# LED_battary.net
KiCad netlist of a schematic drawn in EAGLE
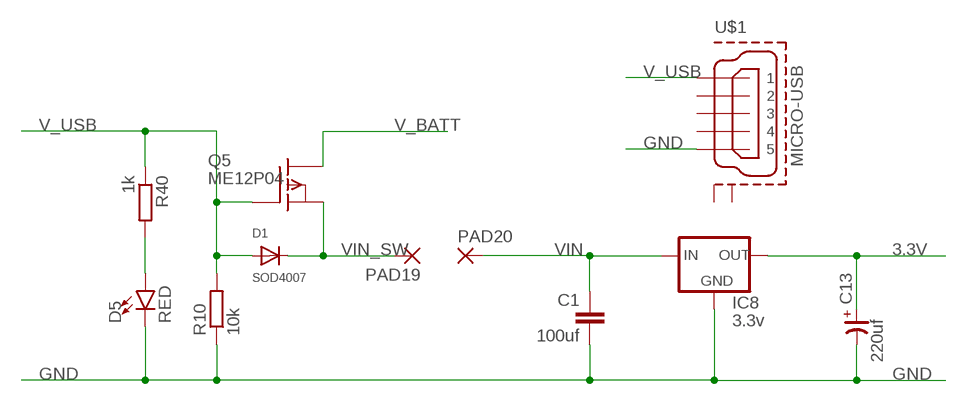
[diagram p0: schematic, sheet 1]
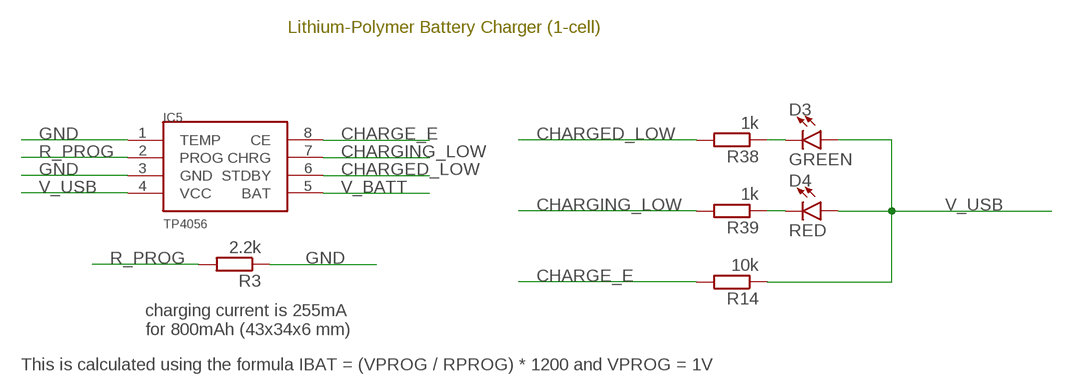
[diagram p1: schematic, sheet 2]
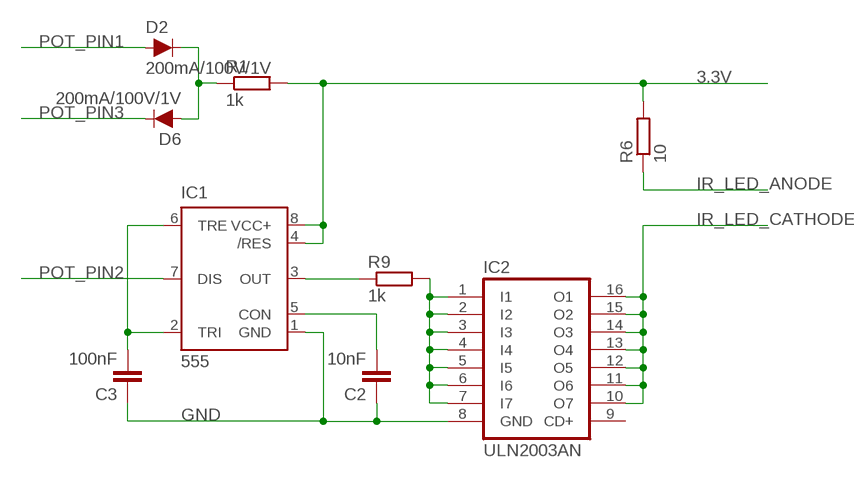
[diagram p2: schematic, sheet 3]
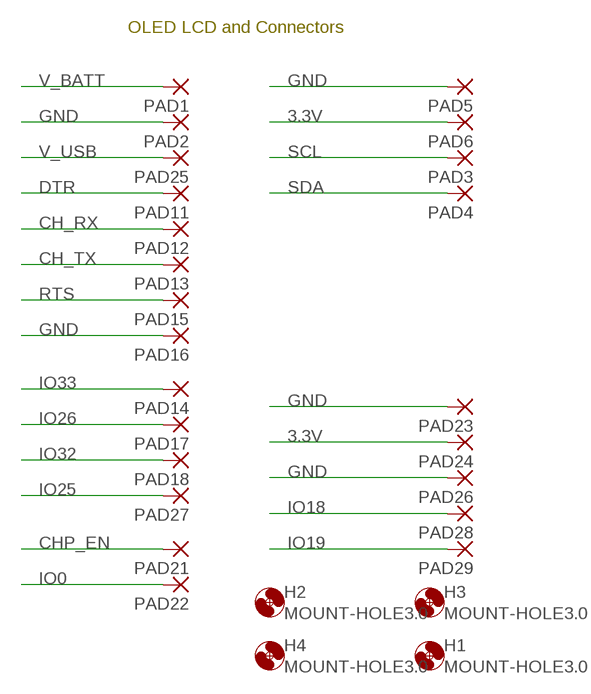
[diagram p3: schematic, sheet 4]

(export (version "E")
  (design (tool "Eeschema 10.0.6"))
  (components
    (comp (ref "D3")
      (value "GREEN")
      (footprint "eagle-import:LED-1206")
      (libsource (lib "eagle-import") (part "LED-GREEN1206"))
    )
    (comp (ref "D4")
      (value "RED")
      (footprint "eagle-import:LED-1206")
      (libsource (lib "eagle-import") (part "LED-GREEN1206"))
    )
    (comp (ref "IC5")
      (value "TP4056")
      (footprint "eagle-import:SOP-8")
      (libsource (lib "eagle-import") (part "TP4056"))
    )
    (comp (ref "R3")
      (value "2.2k")
      (footprint "eagle-import:0207_10")
      (libsource (lib "eagle-import") (part "R-EU_0207/10"))
    )
    (comp (ref "R14")
      (value "10k")
      (footprint "eagle-import:0207_10")
      (libsource (lib "eagle-import") (part "R-EU_0207/10"))
    )
    (comp (ref "R38")
      (value "1k")
      (footprint "eagle-import:0207_10")
      (libsource (lib "eagle-import") (part "R-EU_0207/10"))
    )
    (comp (ref "R39")
      (value "1k")
      (footprint "eagle-import:0207_10")
      (libsource (lib "eagle-import") (part "R-EU_0207/10"))
    )
    (comp (ref "C1")
      (value "100uf")
      (footprint "eagle-import:C1206K")
      (libsource (lib "eagle-import") (part "C-EUC1206K"))
    )
    (comp (ref "C13")
      (value "220uf")
      (footprint "eagle-import:7343_T")
      (libsource (lib "eagle-import") (part "CP-7343"))
    )
    (comp (ref "D1")
      (value "SOD4007")
      (footprint "eagle-import:SOD-123FL")
      (libsource (lib "eagle-import") (part "DIODE_SOD-123FL"))
    )
    (comp (ref "D5")
      (value "RED")
      (footprint "eagle-import:LED-1206")
      (libsource (lib "eagle-import") (part "LED-GREEN1206"))
    )
    (comp (ref "IC8")
      (value "3.3v")
      (footprint "eagle-import:TO252")
      (libsource (lib "eagle-import") (part "LM1117TO252"))
    )
    (comp (ref "PAD19")
      (value "SMD2")
      (footprint "eagle-import:SMD1,27-2,54")
      (libsource (lib "eagle-import") (part "SMD2"))
    )
    (comp (ref "PAD20")
      (value "SMD2")
      (footprint "eagle-import:SMD1,27-2,54")
      (libsource (lib "eagle-import") (part "SMD2"))
    )
    (comp (ref "Q5")
      (value "ME12P04")
      (footprint "eagle-import:TO220")
      (libsource (lib "eagle-import") (part "IRF9530"))
    )
    (comp (ref "R10")
      (value "10k")
      (footprint "eagle-import:0207_10")
      (libsource (lib "eagle-import") (part "R-EU_0207/10"))
    )
    (comp (ref "R40")
      (value "1k")
      (footprint "eagle-import:0207_10")
      (libsource (lib "eagle-import") (part "R-EU_0207/10"))
    )
    (comp (ref "U$1")
      (value "MICRO-USB")
      (footprint "eagle-import:47589-0001")
      (libsource (lib "eagle-import") (part "MICRO-USB-RECEPTACLE47589-0001"))
    )
    (comp (ref "H1")
      (value "MOUNT-HOLE3.0")
      (footprint "eagle-import:3,0")
      (libsource (lib "eagle-import") (part "MOUNT-HOLE3.0"))
    )
    (comp (ref "H2")
      (value "MOUNT-HOLE3.0")
      (footprint "eagle-import:3,0")
      (libsource (lib "eagle-import") (part "MOUNT-HOLE3.0"))
    )
    (comp (ref "H3")
      (value "MOUNT-HOLE3.0")
      (footprint "eagle-import:3,0")
      (libsource (lib "eagle-import") (part "MOUNT-HOLE3.0"))
    )
    (comp (ref "H4")
      (value "MOUNT-HOLE3.0")
      (footprint "eagle-import:3,0")
      (libsource (lib "eagle-import") (part "MOUNT-HOLE3.0"))
    )
    (comp (ref "PAD1")
      (value "WIREPADSMD5-2,5")
      (footprint "eagle-import:5-2,5")
      (libsource (lib "eagle-import") (part "WIREPADSMD5-2,5"))
    )
    (comp (ref "PAD2")
      (value "WIREPADSMD5-2,5")
      (footprint "eagle-import:5-2,5")
      (libsource (lib "eagle-import") (part "WIREPADSMD5-2,5"))
    )
    (comp (ref "PAD3")
      (value "SMD2")
      (footprint "eagle-import:SMD1,27-2,54")
      (libsource (lib "eagle-import") (part "SMD2"))
    )
    (comp (ref "PAD4")
      (value "SMD2")
      (footprint "eagle-import:SMD1,27-2,54")
      (libsource (lib "eagle-import") (part "SMD2"))
    )
    (comp (ref "PAD5")
      (value "SMD2")
      (footprint "eagle-import:SMD1,27-2,54")
      (libsource (lib "eagle-import") (part "SMD2"))
    )
    (comp (ref "PAD6")
      (value "SMD2")
      (footprint "eagle-import:SMD1,27-2,54")
      (libsource (lib "eagle-import") (part "SMD2"))
    )
    (comp (ref "PAD11")
      (value "SMD2")
      (footprint "eagle-import:SMD1,27-2,54")
      (libsource (lib "eagle-import") (part "SMD2"))
    )
    (comp (ref "PAD12")
      (value "SMD2")
      (footprint "eagle-import:SMD1,27-2,54")
      (libsource (lib "eagle-import") (part "SMD2"))
    )
    (comp (ref "PAD13")
      (value "SMD2")
      (footprint "eagle-import:SMD1,27-2,54")
      (libsource (lib "eagle-import") (part "SMD2"))
    )
    (comp (ref "PAD14")
      (value "SMD2")
      (footprint "eagle-import:SMD1,27-2,54")
      (libsource (lib "eagle-import") (part "SMD2"))
    )
    (comp (ref "PAD15")
      (value "SMD2")
      (footprint "eagle-import:SMD1,27-2,54")
      (libsource (lib "eagle-import") (part "SMD2"))
    )
    (comp (ref "PAD16")
      (value "SMD2")
      (footprint "eagle-import:SMD1,27-2,54")
      (libsource (lib "eagle-import") (part "SMD2"))
    )
    (comp (ref "PAD17")
      (value "SMD2")
      (footprint "eagle-import:SMD1,27-2,54")
      (libsource (lib "eagle-import") (part "SMD2"))
    )
    (comp (ref "PAD18")
      (value "SMD2")
      (footprint "eagle-import:SMD1,27-2,54")
      (libsource (lib "eagle-import") (part "SMD2"))
    )
    (comp (ref "PAD21")
      (value "SMD2")
      (footprint "eagle-import:SMD1,27-2,54")
      (libsource (lib "eagle-import") (part "SMD2"))
    )
    (comp (ref "PAD22")
      (value "SMD2")
      (footprint "eagle-import:SMD1,27-2,54")
      (libsource (lib "eagle-import") (part "SMD2"))
    )
    (comp (ref "PAD23")
      (value "SMD2")
      (footprint "eagle-import:SMD1,27-2,54")
      (libsource (lib "eagle-import") (part "SMD2"))
    )
    (comp (ref "PAD24")
      (value "SMD2")
      (footprint "eagle-import:SMD1,27-2,54")
      (libsource (lib "eagle-import") (part "SMD2"))
    )
    (comp (ref "PAD25")
      (value "SMD2")
      (footprint "eagle-import:SMD1,27-2,54")
      (libsource (lib "eagle-import") (part "SMD2"))
    )
    (comp (ref "PAD26")
      (value "SMD2")
      (footprint "eagle-import:SMD1,27-2,54")
      (libsource (lib "eagle-import") (part "SMD2"))
    )
    (comp (ref "PAD27")
      (value "SMD2")
      (footprint "eagle-import:SMD1,27-2,54")
      (libsource (lib "eagle-import") (part "SMD2"))
    )
    (comp (ref "PAD28")
      (value "SMD2")
      (footprint "eagle-import:SMD1,27-2,54")
      (libsource (lib "eagle-import") (part "SMD2"))
    )
    (comp (ref "PAD29")
      (value "SMD2")
      (footprint "eagle-import:SMD1,27-2,54")
      (libsource (lib "eagle-import") (part "SMD2"))
    )
    (comp (ref "C2")
      (value "10nF")
      (footprint "eagle-import:C1206K")
      (libsource (lib "eagle-import") (part "C-EUC1206K"))
    )
    (comp (ref "C3")
      (value "100nF")
      (footprint "eagle-import:C1206K")
      (libsource (lib "eagle-import") (part "C-EUC1206K"))
    )
    (comp (ref "D2")
      (value "200mA/100V/1V")
      (footprint "eagle-import:DIODE-1N4148")
      (libsource (lib "eagle-import") (part "DIODE-1N4148"))
    )
    (comp (ref "D6")
      (value "200mA/100V/1V")
      (footprint "eagle-import:DIODE-1N4148")
      (libsource (lib "eagle-import") (part "DIODE-1N4148"))
    )
    (comp (ref "IC1")
      (value "555")
      (footprint "eagle-import:DIP08")
      (libsource (lib "eagle-import") (part "555P"))
    )
    (comp (ref "IC2")
      (value "ULN2003AN")
      (footprint "eagle-import:DIL16")
      (libsource (lib "eagle-import") (part "ULN2003AN"))
    )
    (comp (ref "R1")
      (value "1k")
      (footprint "eagle-import:0207_10")
      (libsource (lib "eagle-import") (part "R-EU_0207/10"))
    )
    (comp (ref "R6")
      (value "10")
      (footprint "eagle-import:0207_10")
      (libsource (lib "eagle-import") (part "R-EU_0207/10"))
    )
    (comp (ref "R9")
      (value "1k")
      (footprint "eagle-import:0207_10")
      (libsource (lib "eagle-import") (part "R-EU_0207/10"))
    )
  )
  (nets
    (net (code "1") (name "3.3V") (class "Default")
      (node (ref "C13") (pin "+") (pinfunction "+_+") (pintype "passive"))
      (node (ref "IC1") (pin "4") (pinfunction "/RES_4") (pintype "input"))
      (node (ref "IC1") (pin "8") (pinfunction "VCC+_8") (pintype "power_in"))
      (node (ref "IC8") (pin "3") (pinfunction "OUT_3") (pintype "passive"))
      (node (ref "PAD24") (pin "1") (pinfunction "P_1") (pintype "passive"))
      (node (ref "PAD6") (pin "1") (pinfunction "P_1") (pintype "passive"))
      (node (ref "R1") (pin "2") (pinfunction "2_2") (pintype "passive"))
      (node (ref "R6") (pin "2") (pinfunction "2_2") (pintype "passive"))
    )
    (net (code "2") (name "CHARGED_LOW") (class "Default")
      (node (ref "IC5") (pin "6") (pinfunction "STDBY_6") (pintype "bidirectional"))
      (node (ref "R38") (pin "2") (pinfunction "2_2") (pintype "passive"))
    )
    (net (code "3") (name "CHARGE_E") (class "Default")
      (node (ref "IC5") (pin "8") (pinfunction "CE_8") (pintype "bidirectional"))
      (node (ref "R14") (pin "2") (pinfunction "2_2") (pintype "passive"))
    )
    (net (code "4") (name "CHARGING_LOW") (class "Default")
      (node (ref "IC5") (pin "7") (pinfunction "CHRG_7") (pintype "bidirectional"))
      (node (ref "R39") (pin "2") (pinfunction "2_2") (pintype "passive"))
    )
    (net (code "5") (name "CHP_EN") (class "Default")
      (node (ref "PAD21") (pin "1") (pinfunction "P_1") (pintype "passive"))
    )
    (net (code "6") (name "CH_RX") (class "Default")
      (node (ref "PAD12") (pin "1") (pinfunction "P_1") (pintype "passive"))
    )
    (net (code "7") (name "CH_TX") (class "Default")
      (node (ref "PAD13") (pin "1") (pinfunction "P_1") (pintype "passive"))
    )
    (net (code "8") (name "DTR") (class "Default")
      (node (ref "PAD11") (pin "1") (pinfunction "P_1") (pintype "passive"))
    )
    (net (code "9") (name "GND") (class "Default")
      (node (ref "C1") (pin "2") (pinfunction "2_2") (pintype "passive"))
      (node (ref "C13") (pin "-") (pinfunction "-_-") (pintype "passive"))
      (node (ref "C2") (pin "1") (pinfunction "1_1") (pintype "passive"))
      (node (ref "C3") (pin "1") (pinfunction "1_1") (pintype "passive"))
      (node (ref "D5") (pin "C") (pinfunction "C_C") (pintype "passive"))
      (node (ref "IC1") (pin "1") (pinfunction "GND_1") (pintype "power_in"))
      (node (ref "IC2") (pin "8") (pinfunction "GND_8") (pintype "power_in"))
      (node (ref "IC5") (pin "1") (pinfunction "TEMP_1") (pintype "bidirectional"))
      (node (ref "IC5") (pin "3") (pinfunction "GND_3") (pintype "bidirectional"))
      (node (ref "IC8") (pin "1") (pinfunction "GND_1") (pintype "input"))
      (node (ref "PAD16") (pin "1") (pinfunction "P_1") (pintype "passive"))
      (node (ref "PAD2") (pin "1") (pinfunction "P_1") (pintype "passive"))
      (node (ref "PAD23") (pin "1") (pinfunction "P_1") (pintype "passive"))
      (node (ref "PAD26") (pin "1") (pinfunction "P_1") (pintype "passive"))
      (node (ref "PAD5") (pin "1") (pinfunction "P_1") (pintype "passive"))
      (node (ref "R10") (pin "1") (pinfunction "1_1") (pintype "passive"))
      (node (ref "R3") (pin "1") (pinfunction "1_1") (pintype "passive"))
      (node (ref "U$1") (pin "5") (pinfunction "5_5") (pintype "input"))
    )
    (net (code "10") (name "IO0") (class "Default")
      (node (ref "PAD22") (pin "1") (pinfunction "P_1") (pintype "passive"))
    )
    (net (code "11") (name "IO18") (class "Default")
      (node (ref "PAD28") (pin "1") (pinfunction "P_1") (pintype "passive"))
    )
    (net (code "12") (name "IO19") (class "Default")
      (node (ref "PAD29") (pin "1") (pinfunction "P_1") (pintype "passive"))
    )
    (net (code "13") (name "IO25") (class "Default")
      (node (ref "PAD27") (pin "1") (pinfunction "P_1") (pintype "passive"))
    )
    (net (code "14") (name "IO26") (class "Default")
      (node (ref "PAD17") (pin "1") (pinfunction "P_1") (pintype "passive"))
    )
    (net (code "15") (name "IO32") (class "Default")
      (node (ref "PAD18") (pin "1") (pinfunction "P_1") (pintype "passive"))
    )
    (net (code "16") (name "IO33") (class "Default")
      (node (ref "PAD14") (pin "1") (pinfunction "P_1") (pintype "passive"))
    )
    (net (code "17") (name "IR_LED_ANODE") (class "Default")
      (node (ref "R6") (pin "1") (pinfunction "1_1") (pintype "passive"))
    )
    (net (code "18") (name "IR_LED_CATHODE") (class "Default")
      (node (ref "IC2") (pin "10") (pinfunction "O7_10") (pintype "open_collector"))
      (node (ref "IC2") (pin "11") (pinfunction "O6_11") (pintype "open_collector"))
      (node (ref "IC2") (pin "12") (pinfunction "O5_12") (pintype "open_collector"))
      (node (ref "IC2") (pin "13") (pinfunction "O4_13") (pintype "open_collector"))
      (node (ref "IC2") (pin "14") (pinfunction "O3_14") (pintype "open_collector"))
      (node (ref "IC2") (pin "15") (pinfunction "O2_15") (pintype "open_collector"))
      (node (ref "IC2") (pin "16") (pinfunction "O1_16") (pintype "open_collector"))
    )
    (net (code "19") (name "Net-(D2-PadC)") (class "Default")
      (node (ref "D2") (pin "C") (pinfunction "C_C") (pintype "passive"))
      (node (ref "D6") (pin "A") (pinfunction "A_A") (pintype "passive"))
      (node (ref "R1") (pin "1") (pinfunction "1_1") (pintype "passive"))
    )
    (net (code "20") (name "Net-(D3-PadC)") (class "Default")
      (node (ref "D3") (pin "C") (pinfunction "C_C") (pintype "passive"))
      (node (ref "R38") (pin "1") (pinfunction "1_1") (pintype "passive"))
    )
    (net (code "21") (name "Net-(D4-PadC)") (class "Default")
      (node (ref "D4") (pin "C") (pinfunction "C_C") (pintype "passive"))
      (node (ref "R39") (pin "1") (pinfunction "1_1") (pintype "passive"))
    )
    (net (code "22") (name "Net-(D5-PadA)") (class "Default")
      (node (ref "D5") (pin "A") (pinfunction "A_A") (pintype "passive"))
      (node (ref "R40") (pin "2") (pinfunction "2_2") (pintype "passive"))
    )
    (net (code "23") (name "Net-(IC1-CON)") (class "Default")
      (node (ref "C2") (pin "2") (pinfunction "2_2") (pintype "passive"))
      (node (ref "IC1") (pin "5") (pinfunction "CON_5") (pintype "input"))
    )
    (net (code "24") (name "Net-(IC1-OUT)") (class "Default")
      (node (ref "IC1") (pin "3") (pinfunction "OUT_3") (pintype "output"))
      (node (ref "R9") (pin "1") (pinfunction "1_1") (pintype "passive"))
    )
    (net (code "25") (name "Net-(IC1-TRE)") (class "Default")
      (node (ref "C3") (pin "2") (pinfunction "2_2") (pintype "passive"))
      (node (ref "IC1") (pin "2") (pinfunction "TRI_2") (pintype "input"))
      (node (ref "IC1") (pin "6") (pinfunction "TRE_6") (pintype "input"))
    )
    (net (code "26") (name "Net-(IC2-I1)") (class "Default")
      (node (ref "IC2") (pin "1") (pinfunction "I1_1") (pintype "input"))
      (node (ref "IC2") (pin "2") (pinfunction "I2_2") (pintype "input"))
      (node (ref "IC2") (pin "3") (pinfunction "I3_3") (pintype "input"))
      (node (ref "IC2") (pin "4") (pinfunction "I4_4") (pintype "input"))
      (node (ref "IC2") (pin "5") (pinfunction "I5_5") (pintype "input"))
      (node (ref "IC2") (pin "6") (pinfunction "I6_6") (pintype "input"))
      (node (ref "IC2") (pin "7") (pinfunction "I7_7") (pintype "input"))
      (node (ref "R9") (pin "2") (pinfunction "2_2") (pintype "passive"))
    )
    (net (code "27") (name "POT_PIN1") (class "Default")
      (node (ref "D2") (pin "A") (pinfunction "A_A") (pintype "passive"))
    )
    (net (code "28") (name "POT_PIN2") (class "Default")
      (node (ref "IC1") (pin "7") (pinfunction "DIS_7") (pintype "input"))
    )
    (net (code "29") (name "POT_PIN3") (class "Default")
      (node (ref "D6") (pin "C") (pinfunction "C_C") (pintype "passive"))
    )
    (net (code "30") (name "RTS") (class "Default")
      (node (ref "PAD15") (pin "1") (pinfunction "P_1") (pintype "passive"))
    )
    (net (code "31") (name "R_PROG") (class "Default")
      (node (ref "IC5") (pin "2") (pinfunction "PROG_2") (pintype "bidirectional"))
      (node (ref "R3") (pin "2") (pinfunction "2_2") (pintype "passive"))
    )
    (net (code "32") (name "SCL") (class "Default")
      (node (ref "PAD3") (pin "1") (pinfunction "P_1") (pintype "passive"))
    )
    (net (code "33") (name "SDA") (class "Default")
      (node (ref "PAD4") (pin "1") (pinfunction "P_1") (pintype "passive"))
    )
    (net (code "34") (name "VIN") (class "Default")
      (node (ref "C1") (pin "1") (pinfunction "1_1") (pintype "passive"))
      (node (ref "IC8") (pin "2") (pinfunction "IN_2") (pintype "input"))
      (node (ref "PAD20") (pin "1") (pinfunction "P_1") (pintype "passive"))
    )
    (net (code "35") (name "VIN_SW") (class "Default")
      (node (ref "D1") (pin "C") (pinfunction "C_C") (pintype "passive"))
      (node (ref "PAD19") (pin "1") (pinfunction "P_1") (pintype "passive"))
      (node (ref "Q5") (pin "3") (pinfunction "S_3") (pintype "passive"))
    )
    (net (code "36") (name "V_BATT") (class "Default")
      (node (ref "IC5") (pin "5") (pinfunction "BAT_5") (pintype "bidirectional"))
      (node (ref "PAD1") (pin "1") (pinfunction "P_1") (pintype "passive"))
      (node (ref "Q5") (pin "2") (pinfunction "D_2") (pintype "passive"))
    )
    (net (code "37") (name "V_USB") (class "Default")
      (node (ref "D1") (pin "A") (pinfunction "A_A") (pintype "passive"))
      (node (ref "D3") (pin "A") (pinfunction "A_A") (pintype "passive"))
      (node (ref "D4") (pin "A") (pinfunction "A_A") (pintype "passive"))
      (node (ref "IC5") (pin "4") (pinfunction "VCC_4") (pintype "bidirectional"))
      (node (ref "PAD25") (pin "1") (pinfunction "P_1") (pintype "passive"))
      (node (ref "Q5") (pin "1") (pinfunction "G_1") (pintype "passive"))
      (node (ref "R10") (pin "2") (pinfunction "2_2") (pintype "passive"))
      (node (ref "R14") (pin "1") (pinfunction "1_1") (pintype "passive"))
      (node (ref "R40") (pin "1") (pinfunction "1_1") (pintype "passive"))
      (node (ref "U$1") (pin "1") (pinfunction "1_1") (pintype "input"))
    )
    (net (code "38") (name "unconnected-(IC2-CD+-Pad9)") (class "Default")
      (node (ref "IC2") (pin "9") (pinfunction "CD+_9") (pintype "passive"))
    )
    (net (code "39") (name "unconnected-(U$1-GND1-PadP$1)") (class "Default")
      (node (ref "U$1") (pin "P$1") (pinfunction "GND1_P$1") (pintype "bidirectional"))
    )
    (net (code "40") (name "unconnected-(U$1-GND2-PadP$2)") (class "Default")
      (node (ref "U$1") (pin "P$2") (pinfunction "GND2_P$2") (pintype "bidirectional"))
    )
    (net (code "41") (name "unconnected-(U$1-Pad2)") (class "Default")
      (node (ref "U$1") (pin "2") (pinfunction "2_2") (pintype "input"))
    )
    (net (code "42") (name "unconnected-(U$1-Pad3)") (class "Default")
      (node (ref "U$1") (pin "3") (pinfunction "3_3") (pintype "input"))
    )
    (net (code "43") (name "unconnected-(U$1-Pad4)") (class "Default")
      (node (ref "U$1") (pin "4") (pinfunction "4_4") (pintype "input"))
    )
  )
)
